# SCH_Flight-Computer-V2_2024-07-15.net
KiCad netlist of a schematic drawn in EasyEDA
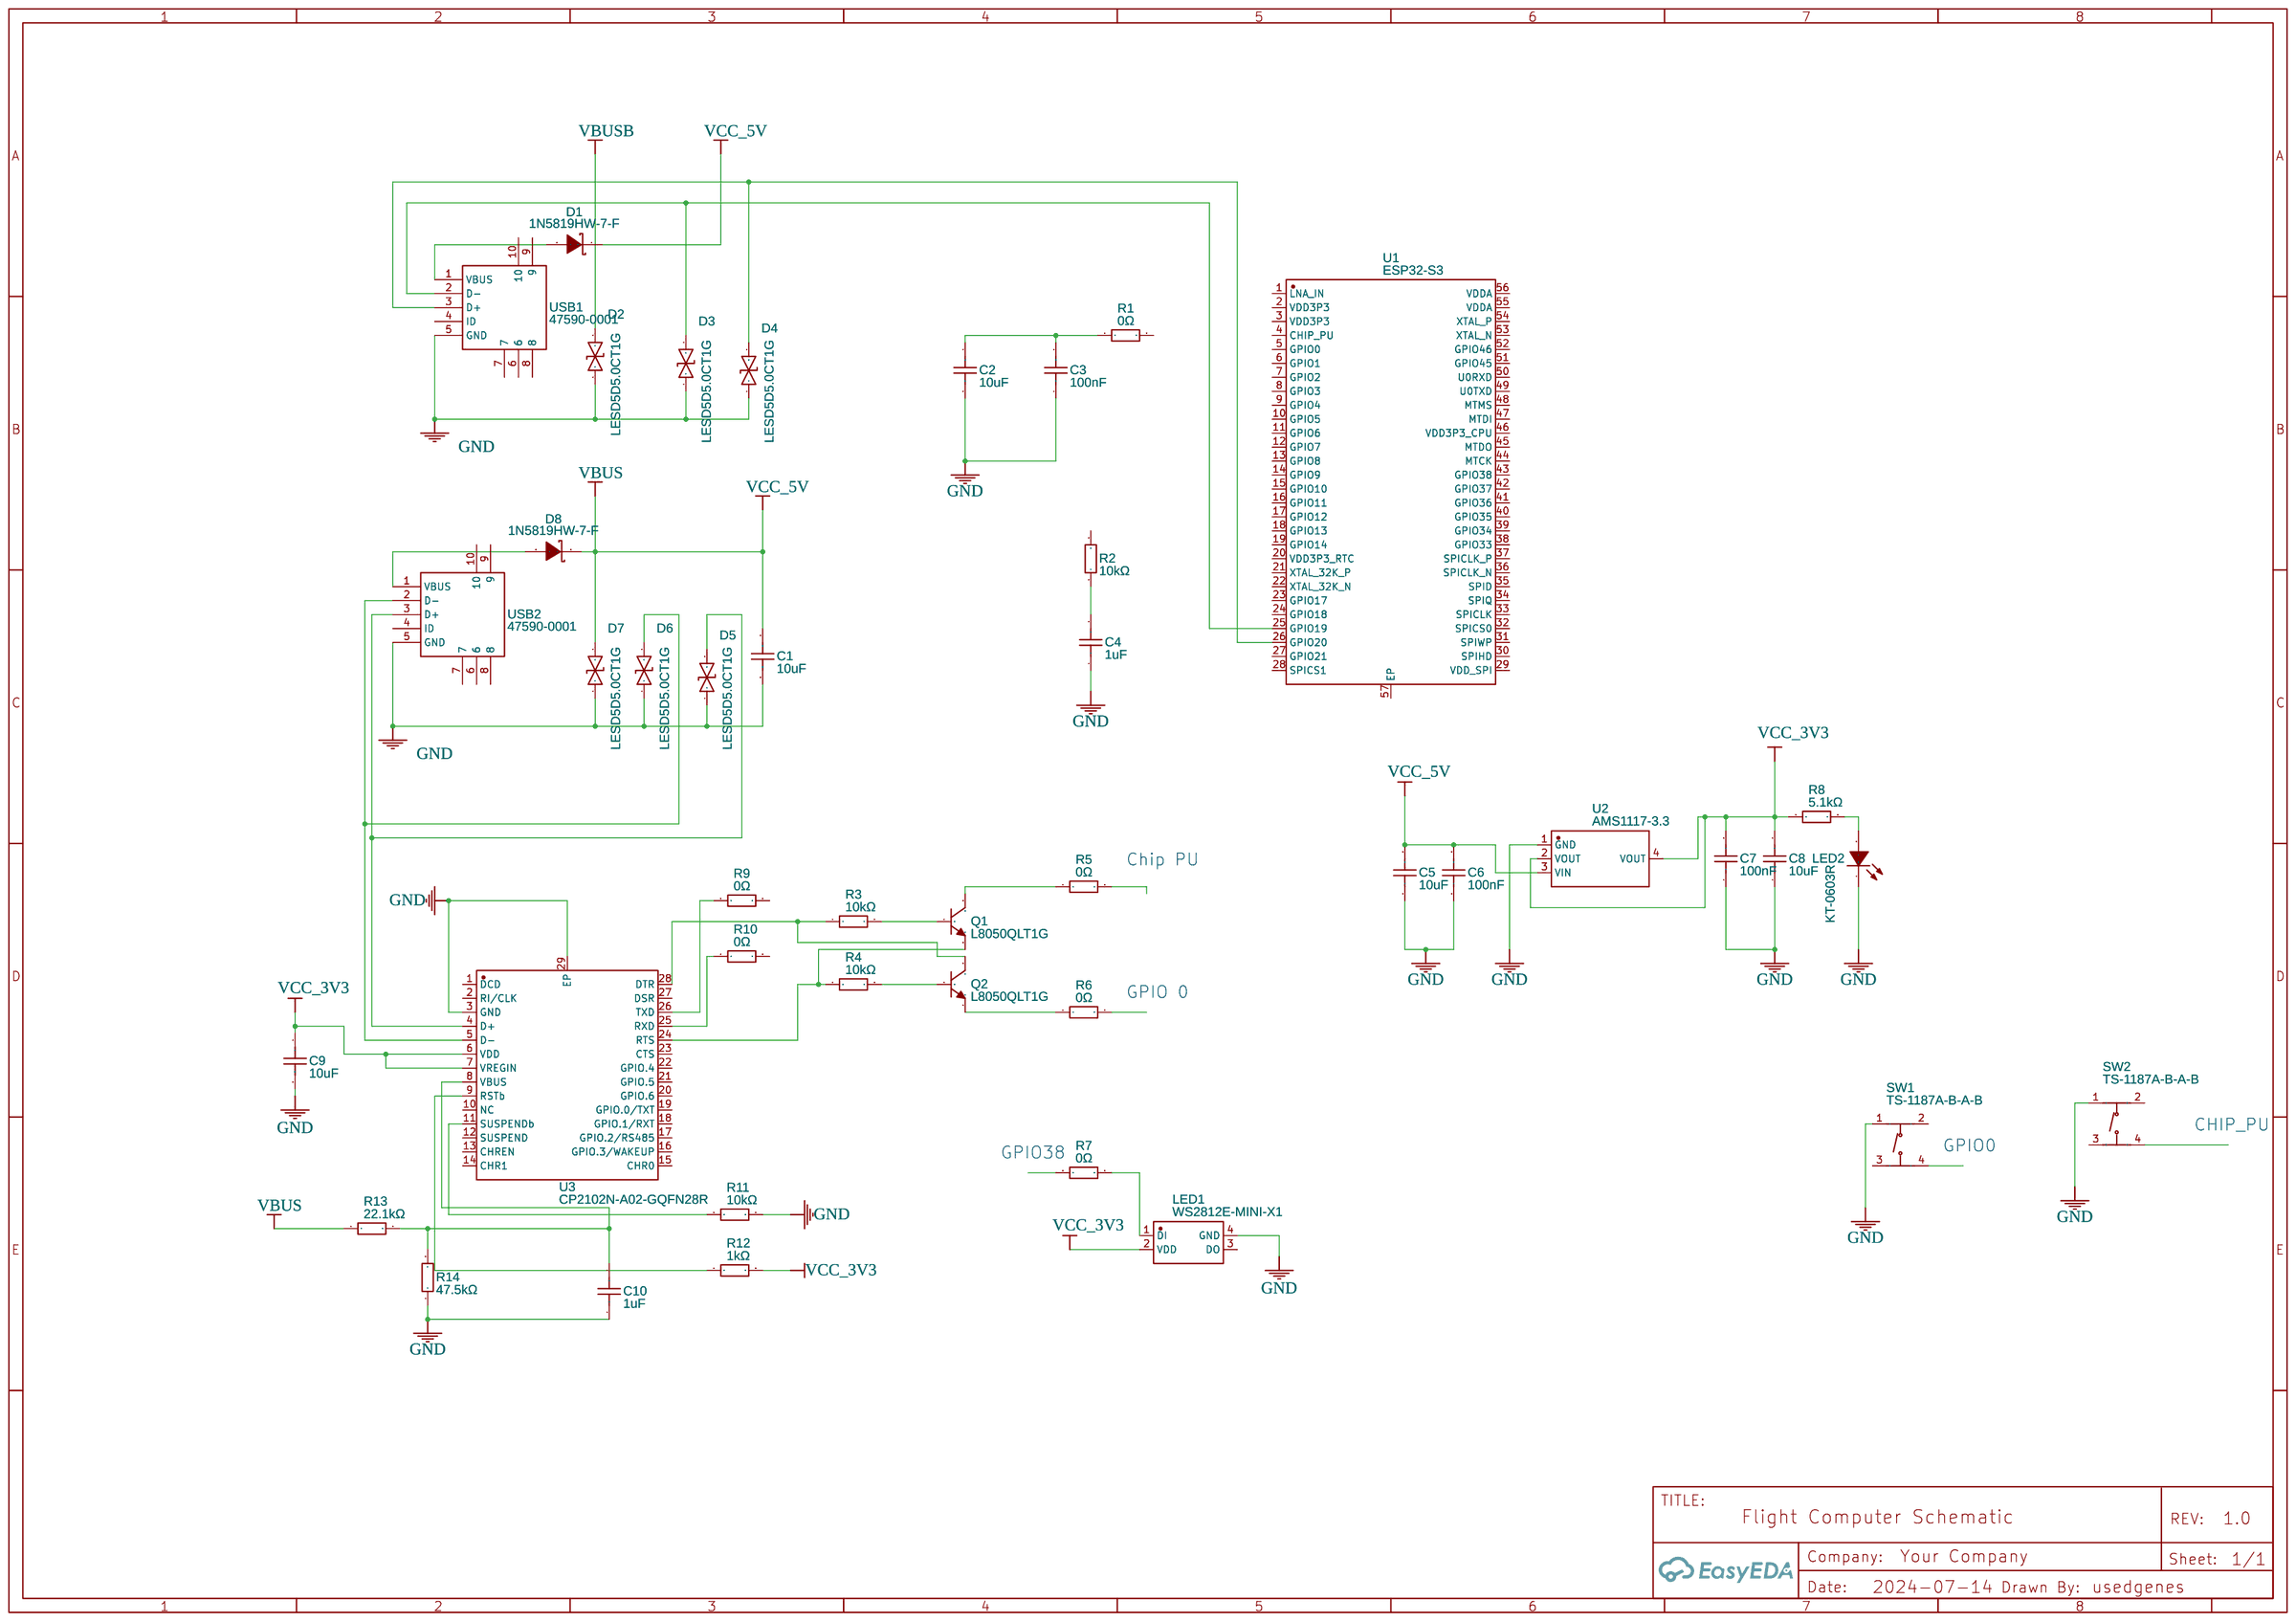
[diagram p0: schematic sheet]

(export (version "E")
  (design (tool "Eeschema 10.0.6"))
  (components
    (comp (ref "C1")
      (value "10uF")
      (fields
        (field (name "Manufacturer Part") "CL10A106KP8NNNC")
        (field (name "Manufacturer") "SAMSUNG(三星)")
      )
      (libsource (lib "") (part "CL10A106KP8NNNC"))
    )
    (comp (ref "C2")
      (value "10uF")
      (fields
        (field (name "Manufacturer Part") "CL10A106KP8NNNC")
        (field (name "Manufacturer") "SAMSUNG(三星)")
      )
      (libsource (lib "") (part "CL10A106KP8NNNC"))
    )
    (comp (ref "C3")
      (value "100nF")
      (fields
        (field (name "Manufacturer Part") "CC0603KRX7R9BB104")
        (field (name "Manufacturer") "YAGEO(国巨)")
      )
      (libsource (lib "") (part "CC0603KRX7R9BB104"))
    )
    (comp (ref "C4")
      (value "1uF")
      (fields
        (field (name "Manufacturer Part") "CL10A105KB8NNNC")
        (field (name "Manufacturer") "SAMSUNG(三星)")
      )
      (libsource (lib "") (part "CL10A105KB8NNNC"))
    )
    (comp (ref "C5")
      (value "10uF")
      (fields
        (field (name "Manufacturer Part") "CL10A106KP8NNNC")
        (field (name "Manufacturer") "SAMSUNG(三星)")
      )
      (libsource (lib "") (part "CL10A106KP8NNNC_1"))
    )
    (comp (ref "C6")
      (value "100nF")
      (fields
        (field (name "Manufacturer Part") "CC0603KRX7R9BB104")
        (field (name "Manufacturer") "YAGEO(国巨)")
      )
      (libsource (lib "") (part "CC0603KRX7R9BB104"))
    )
    (comp (ref "C7")
      (value "100nF")
      (fields
        (field (name "Manufacturer Part") "CC0603KRX7R9BB104")
        (field (name "Manufacturer") "YAGEO(国巨)")
      )
      (libsource (lib "") (part "CC0603KRX7R9BB104"))
    )
    (comp (ref "C8")
      (value "10uF")
      (fields
        (field (name "Manufacturer Part") "CL10A106KP8NNNC")
        (field (name "Manufacturer") "SAMSUNG(三星)")
      )
      (libsource (lib "") (part "CL10A106KP8NNNC_1"))
    )
    (comp (ref "C9")
      (value "10uF")
      (fields
        (field (name "Manufacturer Part") "CL10A106KP8NNNC")
        (field (name "Manufacturer") "SAMSUNG(三星)")
      )
      (libsource (lib "") (part "CL10A106KP8NNNC"))
    )
    (comp (ref "C10")
      (value "1uF")
      (fields
        (field (name "Manufacturer Part") "CL10A105KB8NNNC")
        (field (name "Manufacturer") "SAMSUNG(三星)")
      )
      (libsource (lib "") (part "CL10A105KB8NNNC"))
    )
    (comp (ref "D1")
      (value "1N5819HW-7-F")
      (fields (field (name "Manufacturer") "DIODES(美台)"))
      (libsource (lib "") (part "1N5819HW-7-F"))
    )
    (comp (ref "D2")
      (value "LESD5D5.0CT1G")
      (fields (field (name "Manufacturer") "LRC(乐山无线电)"))
      (libsource (lib "") (part "LESD5D5.0CT1G"))
    )
    (comp (ref "D3")
      (value "LESD5D5.0CT1G")
      (fields (field (name "Manufacturer") "LRC(乐山无线电)"))
      (libsource (lib "") (part "LESD5D5.0CT1G"))
    )
    (comp (ref "D4")
      (value "LESD5D5.0CT1G")
      (fields (field (name "Manufacturer") "LRC(乐山无线电)"))
      (libsource (lib "") (part "LESD5D5.0CT1G"))
    )
    (comp (ref "D5")
      (value "LESD5D5.0CT1G")
      (fields (field (name "Manufacturer") "LRC(乐山无线电)"))
      (libsource (lib "") (part "LESD5D5.0CT1G"))
    )
    (comp (ref "D6")
      (value "LESD5D5.0CT1G")
      (fields (field (name "Manufacturer") "LRC(乐山无线电)"))
      (libsource (lib "") (part "LESD5D5.0CT1G"))
    )
    (comp (ref "D7")
      (value "LESD5D5.0CT1G")
      (fields (field (name "Manufacturer") "LRC(乐山无线电)"))
      (libsource (lib "") (part "LESD5D5.0CT1G"))
    )
    (comp (ref "D8")
      (value "1N5819HW-7-F")
      (fields (field (name "Manufacturer") "DIODES(美台)"))
      (libsource (lib "") (part "1N5819HW-7-F"))
    )
    (comp (ref "LED1")
      (value "WS2812E-MINI-X1")
      (fields (field (name "Manufacturer") "worldsemi"))
      (libsource (lib "") (part "WS2812E-MINI-X1"))
    )
    (comp (ref "LED2")
      (value "KT-0603R")
      (fields (field (name "Manufacturer") "KENTO"))
      (libsource (lib "") (part "KT-0603R"))
    )
    (comp (ref "Q1")
      (value "L8050QLT1G")
      (fields (field (name "Manufacturer") "LRC(乐山无线电)"))
      (libsource (lib "") (part "L8050QLT1G"))
    )
    (comp (ref "Q2")
      (value "L8050QLT1G")
      (fields (field (name "Manufacturer") "LRC(乐山无线电)"))
      (libsource (lib "") (part "L8050QLT1G"))
    )
    (comp (ref "R1")
      (value "0Ω")
      (fields
        (field (name "Manufacturer Part") "0402WGF0000TCE")
        (field (name "Manufacturer") "UNI-ROYAL(厚声)")
      )
      (libsource (lib "") (part "0402WGF0000TCE"))
    )
    (comp (ref "R2")
      (value "10kΩ")
      (fields
        (field (name "Manufacturer Part") "0603WAF1002T5E")
        (field (name "Manufacturer") "UNI-ROYAL(厚声)")
      )
      (libsource (lib "") (part "0603WAF1002T5E_1"))
    )
    (comp (ref "R3")
      (value "10kΩ")
      (fields
        (field (name "Manufacturer Part") "0603WAF1002T5E")
        (field (name "Manufacturer") "UNI-ROYAL(厚声)")
      )
      (libsource (lib "") (part "0603WAF1002T5E"))
    )
    (comp (ref "R4")
      (value "10kΩ")
      (fields
        (field (name "Manufacturer Part") "0603WAF1002T5E")
        (field (name "Manufacturer") "UNI-ROYAL(厚声)")
      )
      (libsource (lib "") (part "0603WAF1002T5E"))
    )
    (comp (ref "R5")
      (value "0Ω")
      (fields
        (field (name "Manufacturer Part") "0402WGF0000TCE")
        (field (name "Manufacturer") "UNI-ROYAL(厚声)")
      )
      (libsource (lib "") (part "0402WGF0000TCE"))
    )
    (comp (ref "R6")
      (value "0Ω")
      (fields
        (field (name "Manufacturer Part") "0402WGF0000TCE")
        (field (name "Manufacturer") "UNI-ROYAL(厚声)")
      )
      (libsource (lib "") (part "0402WGF0000TCE"))
    )
    (comp (ref "R7")
      (value "0Ω")
      (fields
        (field (name "Manufacturer Part") "0402WGF0000TCE")
        (field (name "Manufacturer") "UNI-ROYAL(厚声)")
      )
      (libsource (lib "") (part "0402WGF0000TCE"))
    )
    (comp (ref "R8")
      (value "5.1kΩ")
      (fields
        (field (name "Manufacturer Part") "0603WAF5101T5E")
        (field (name "Manufacturer") "UNI-ROYAL(厚声)")
      )
      (libsource (lib "") (part "0603WAF5101T5E"))
    )
    (comp (ref "R9")
      (value "0Ω")
      (fields
        (field (name "Manufacturer Part") "0402WGF0000TCE")
        (field (name "Manufacturer") "UNI-ROYAL(厚声)")
      )
      (libsource (lib "") (part "0402WGF0000TCE"))
    )
    (comp (ref "R10")
      (value "0Ω")
      (fields
        (field (name "Manufacturer Part") "0402WGF0000TCE")
        (field (name "Manufacturer") "UNI-ROYAL(厚声)")
      )
      (libsource (lib "") (part "0402WGF0000TCE"))
    )
    (comp (ref "R11")
      (value "10kΩ")
      (fields
        (field (name "Manufacturer Part") "0603WAF1002T5E")
        (field (name "Manufacturer") "UNI-ROYAL(厚声)")
      )
      (libsource (lib "") (part "0603WAF1002T5E"))
    )
    (comp (ref "R12")
      (value "1kΩ")
      (fields
        (field (name "Manufacturer Part") "0603WAF1001T5E")
        (field (name "Manufacturer") "UNI-ROYAL(厚声)")
      )
      (libsource (lib "") (part "0603WAF1001T5E"))
    )
    (comp (ref "R13")
      (value "22.1kΩ")
      (fields
        (field (name "Manufacturer Part") "0402WGF2212TCE")
        (field (name "Manufacturer") "UNI-ROYAL(厚声)")
      )
      (libsource (lib "") (part "0402WGF2212TCE"))
    )
    (comp (ref "R14")
      (value "47.5kΩ")
      (fields
        (field (name "Manufacturer Part") "0603WAF4752T5E")
        (field (name "Manufacturer") "UNI-ROYAL(厚声)")
      )
      (libsource (lib "") (part "0603WAF4752T5E"))
    )
    (comp (ref "SW1")
      (value "TS-1187A-B-A-B")
      (fields (field (name "Manufacturer") "XKB Connectivity(中国星坤)"))
      (libsource (lib "") (part "TS-1187A-B-A-B"))
    )
    (comp (ref "SW2")
      (value "TS-1187A-B-A-B")
      (fields (field (name "Manufacturer") "XKB Connectivity(中国星坤)"))
      (libsource (lib "") (part "TS-1187A-B-A-B"))
    )
    (comp (ref "U1")
      (value "ESP32-S3")
      (fields (field (name "Manufacturer") "ESPRESSIF(乐鑫)"))
      (libsource (lib "") (part "ESP32-S3"))
    )
    (comp (ref "U2")
      (value "AMS1117-3.3")
      (fields (field (name "Manufacturer") "AMS"))
      (libsource (lib "") (part "AMS1117-3.3"))
    )
    (comp (ref "U3")
      (value "CP2102N-A02-GQFN28R")
      (fields (field (name "Manufacturer") "SKYWORKS/SILICON LABS(芯科)"))
      (libsource (lib "") (part "CP2102N-A02-GQFN28R"))
    )
    (comp (ref "USB1")
      (value "47590-0001")
      (fields (field (name "Manufacturer Part") "475900001") (field (name "Manufacturer") "MOLEX"))
      (libsource (lib "") (part "47590-0001"))
    )
    (comp (ref "USB2")
      (value "47590-0001")
      (fields (field (name "Manufacturer Part") "475900001") (field (name "Manufacturer") "MOLEX"))
      (libsource (lib "") (part "47590-0001"))
    )
  )
  (nets
    (net (code "1") (name "GND") (class "Default")
      (node (ref "C1") (pin "2") (pinfunction "2_2") (pintype "unspecified"))
      (node (ref "C10") (pin "1") (pinfunction "1_1") (pintype "unspecified"))
      (node (ref "C2") (pin "2") (pinfunction "2_2") (pintype "unspecified"))
      (node (ref "C3") (pin "1") (pinfunction "1_1") (pintype "unspecified"))
      (node (ref "C4") (pin "1") (pinfunction "1_1") (pintype "unspecified"))
      (node (ref "C5") (pin "1") (pinfunction "1_1") (pintype "unspecified"))
      (node (ref "C6") (pin "1") (pinfunction "1_1") (pintype "unspecified"))
      (node (ref "C7") (pin "1") (pinfunction "1_1") (pintype "unspecified"))
      (node (ref "C8") (pin "1") (pinfunction "1_1") (pintype "unspecified"))
      (node (ref "C9") (pin "2") (pinfunction "2_2") (pintype "unspecified"))
      (node (ref "D2") (pin "1") (pinfunction "1_1") (pintype "unspecified"))
      (node (ref "D3") (pin "1") (pinfunction "1_1") (pintype "unspecified"))
      (node (ref "D4") (pin "1") (pinfunction "1_1") (pintype "unspecified"))
      (node (ref "D5") (pin "1") (pinfunction "1_1") (pintype "unspecified"))
      (node (ref "D6") (pin "1") (pinfunction "1_1") (pintype "unspecified"))
      (node (ref "D7") (pin "1") (pinfunction "1_1") (pintype "unspecified"))
      (node (ref "LED1") (pin "4") (pinfunction "GND_4") (pintype "unspecified"))
      (node (ref "LED2") (pin "1") (pinfunction "K_1") (pintype "unspecified"))
      (node (ref "R11") (pin "2") (pinfunction "2_2") (pintype "input"))
      (node (ref "R14") (pin "1") (pinfunction "1_1") (pintype "input"))
      (node (ref "SW1") (pin "1") (pinfunction "A_1") (pintype "unspecified"))
      (node (ref "SW2") (pin "1") (pinfunction "A_1") (pintype "unspecified"))
      (node (ref "U2") (pin "1") (pinfunction "GND_1") (pintype "unspecified"))
      (node (ref "U3") (pin "29") (pinfunction "EP_29") (pintype "unspecified"))
      (node (ref "U3") (pin "3") (pinfunction "GND_3") (pintype "unspecified"))
      (node (ref "USB1") (pin "5") (pinfunction "GND_5") (pintype "unspecified"))
      (node (ref "USB2") (pin "5") (pinfunction "GND_5") (pintype "unspecified"))
    )
    (net (code "2") (name "Net-(C2-Pad1)") (class "Default")
      (node (ref "C2") (pin "1") (pinfunction "1_1") (pintype "unspecified"))
      (node (ref "C3") (pin "2") (pinfunction "2_2") (pintype "unspecified"))
      (node (ref "R1") (pin "1") (pinfunction "1_1") (pintype "input"))
    )
    (net (code "3") (name "Net-(C4-Pad2)") (class "Default")
      (node (ref "C4") (pin "2") (pinfunction "2_2") (pintype "unspecified"))
      (node (ref "R2") (pin "1") (pinfunction "1_1") (pintype "input"))
    )
    (net (code "4") (name "Net-(D1-A)") (class "Default")
      (node (ref "D1") (pin "2") (pinfunction "A_2") (pintype "unspecified"))
      (node (ref "USB1") (pin "1") (pinfunction "VBUS_1") (pintype "unspecified"))
    )
    (net (code "5") (name "Net-(D8-A)") (class "Default")
      (node (ref "D8") (pin "2") (pinfunction "A_2") (pintype "unspecified"))
      (node (ref "USB2") (pin "1") (pinfunction "VBUS_1") (pintype "unspecified"))
    )
    (net (code "6") (name "Net-(LED1-DI)") (class "Default")
      (node (ref "LED1") (pin "1") (pinfunction "DI_1") (pintype "unspecified"))
      (node (ref "R7") (pin "2") (pinfunction "2_2") (pintype "input"))
    )
    (net (code "7") (name "Net-(LED2-A)") (class "Default")
      (node (ref "LED2") (pin "2") (pinfunction "A_2") (pintype "unspecified"))
      (node (ref "R8") (pin "2") (pinfunction "2_2") (pintype "input"))
    )
    (net (code "8") (name "Net-(Q1-B)") (class "Default")
      (node (ref "Q1") (pin "1") (pinfunction "B_1") (pintype "unspecified"))
      (node (ref "R3") (pin "2") (pinfunction "2_2") (pintype "input"))
    )
    (net (code "9") (name "Net-(Q1-C)") (class "Default")
      (node (ref "Q1") (pin "3") (pinfunction "C_3") (pintype "unspecified"))
      (node (ref "R5") (pin "1") (pinfunction "1_1") (pintype "input"))
    )
    (net (code "10") (name "Net-(Q1-E)") (class "Default")
      (node (ref "Q1") (pin "2") (pinfunction "E_2") (pintype "unspecified"))
      (node (ref "R4") (pin "1") (pinfunction "1_1") (pintype "input"))
      (node (ref "U3") (pin "24") (pinfunction "RTS_24") (pintype "unspecified"))
    )
    (net (code "11") (name "Net-(Q2-B)") (class "Default")
      (node (ref "Q2") (pin "1") (pinfunction "B_1") (pintype "unspecified"))
      (node (ref "R4") (pin "2") (pinfunction "2_2") (pintype "input"))
    )
    (net (code "12") (name "Net-(Q2-C)") (class "Default")
      (node (ref "Q2") (pin "3") (pinfunction "C_3") (pintype "unspecified"))
      (node (ref "R3") (pin "1") (pinfunction "1_1") (pintype "input"))
      (node (ref "U3") (pin "28") (pinfunction "DTR_28") (pintype "unspecified"))
    )
    (net (code "13") (name "Net-(Q2-E)") (class "Default")
      (node (ref "Q2") (pin "2") (pinfunction "E_2") (pintype "unspecified"))
      (node (ref "R6") (pin "1") (pinfunction "1_1") (pintype "input"))
    )
    (net (code "14") (name "Net-(U1-GPIO19)") (class "Default")
      (node (ref "D3") (pin "2") (pinfunction "2_2") (pintype "unspecified"))
      (node (ref "U1") (pin "25") (pinfunction "GPIO19_25") (pintype "unspecified"))
      (node (ref "USB1") (pin "2") (pinfunction "D-_2") (pintype "unspecified"))
    )
    (net (code "15") (name "Net-(U1-GPIO20)") (class "Default")
      (node (ref "D4") (pin "2") (pinfunction "2_2") (pintype "unspecified"))
      (node (ref "U1") (pin "26") (pinfunction "GPIO20_26") (pintype "unspecified"))
      (node (ref "USB1") (pin "3") (pinfunction "D+_3") (pintype "unspecified"))
    )
    (net (code "16") (name "Net-(U3-D+)") (class "Default")
      (node (ref "D5") (pin "2") (pinfunction "2_2") (pintype "unspecified"))
      (node (ref "U3") (pin "4") (pinfunction "D+_4") (pintype "unspecified"))
      (node (ref "USB2") (pin "3") (pinfunction "D+_3") (pintype "unspecified"))
    )
    (net (code "17") (name "Net-(U3-D-)") (class "Default")
      (node (ref "D6") (pin "2") (pinfunction "2_2") (pintype "unspecified"))
      (node (ref "U3") (pin "5") (pinfunction "D-_5") (pintype "unspecified"))
      (node (ref "USB2") (pin "2") (pinfunction "D-_2") (pintype "unspecified"))
    )
    (net (code "18") (name "Net-(U3-RSTb)") (class "Default")
      (node (ref "R12") (pin "1") (pinfunction "1_1") (pintype "input"))
      (node (ref "U3") (pin "9") (pinfunction "RSTb_9") (pintype "unspecified"))
    )
    (net (code "19") (name "Net-(U3-RXD)") (class "Default")
      (node (ref "R10") (pin "1") (pinfunction "1_1") (pintype "input"))
      (node (ref "U3") (pin "25") (pinfunction "RXD_25") (pintype "unspecified"))
    )
    (net (code "20") (name "Net-(U3-SUSPENDb)") (class "Default")
      (node (ref "R11") (pin "1") (pinfunction "1_1") (pintype "input"))
      (node (ref "U3") (pin "11") (pinfunction "SUSPENDb_11") (pintype "unspecified"))
    )
    (net (code "21") (name "Net-(U3-TXD)") (class "Default")
      (node (ref "R9") (pin "1") (pinfunction "1_1") (pintype "input"))
      (node (ref "U3") (pin "26") (pinfunction "TXD_26") (pintype "unspecified"))
    )
    (net (code "22") (name "Net-(U3-VBUS)") (class "Default")
      (node (ref "C10") (pin "2") (pinfunction "2_2") (pintype "unspecified"))
      (node (ref "R13") (pin "2") (pinfunction "2_2") (pintype "input"))
      (node (ref "R14") (pin "2") (pinfunction "2_2") (pintype "input"))
      (node (ref "U3") (pin "8") (pinfunction "VBUS_8") (pintype "unspecified"))
    )
    (net (code "23") (name "VBUS") (class "Default")
      (node (ref "C1") (pin "1") (pinfunction "1_1") (pintype "unspecified"))
      (node (ref "C5") (pin "2") (pinfunction "2_2") (pintype "unspecified"))
      (node (ref "C6") (pin "2") (pinfunction "2_2") (pintype "unspecified"))
      (node (ref "D1") (pin "1") (pinfunction "K_1") (pintype "unspecified"))
      (node (ref "D7") (pin "2") (pinfunction "2_2") (pintype "unspecified"))
      (node (ref "D8") (pin "1") (pinfunction "K_1") (pintype "unspecified"))
      (node (ref "R13") (pin "1") (pinfunction "1_1") (pintype "input"))
      (node (ref "U2") (pin "3") (pinfunction "VIN_3") (pintype "unspecified"))
    )
    (net (code "24") (name "VBUSB") (class "Default")
      (node (ref "D2") (pin "2") (pinfunction "2_2") (pintype "unspecified"))
    )
    (net (code "25") (name "VCC_3V3") (class "Default")
      (node (ref "C7") (pin "2") (pinfunction "2_2") (pintype "unspecified"))
      (node (ref "C8") (pin "2") (pinfunction "2_2") (pintype "unspecified"))
      (node (ref "C9") (pin "1") (pinfunction "1_1") (pintype "unspecified"))
      (node (ref "LED1") (pin "2") (pinfunction "VDD_2") (pintype "unspecified"))
      (node (ref "R12") (pin "2") (pinfunction "2_2") (pintype "input"))
      (node (ref "R8") (pin "1") (pinfunction "1_1") (pintype "input"))
      (node (ref "U2") (pin "2") (pinfunction "VOUT_2") (pintype "unspecified"))
      (node (ref "U2") (pin "4") (pinfunction "VOUT_4") (pintype "unspecified"))
      (node (ref "U3") (pin "6") (pinfunction "VDD_6") (pintype "unspecified"))
      (node (ref "U3") (pin "7") (pinfunction "VREGIN_7") (pintype "unspecified"))
    )
    (net (code "26") (name "unconnected-(LED1-DO-Pad3)") (class "Default")
      (node (ref "LED1") (pin "3") (pinfunction "DO_3") (pintype "unspecified"))
    )
    (net (code "27") (name "unconnected-(R1-Pad2)") (class "Default")
      (node (ref "R1") (pin "2") (pinfunction "2_2") (pintype "input"))
    )
    (net (code "28") (name "unconnected-(R2-Pad2)") (class "Default")
      (node (ref "R2") (pin "2") (pinfunction "2_2") (pintype "input"))
    )
    (net (code "29") (name "unconnected-(R5-Pad2)") (class "Default")
      (node (ref "R5") (pin "2") (pinfunction "2_2") (pintype "input"))
    )
    (net (code "30") (name "unconnected-(R6-Pad2)") (class "Default")
      (node (ref "R6") (pin "2") (pinfunction "2_2") (pintype "input"))
    )
    (net (code "31") (name "unconnected-(R7-Pad1)") (class "Default")
      (node (ref "R7") (pin "1") (pinfunction "1_1") (pintype "input"))
    )
    (net (code "32") (name "unconnected-(R9-Pad2)") (class "Default")
      (node (ref "R9") (pin "2") (pinfunction "2_2") (pintype "input"))
    )
    (net (code "33") (name "unconnected-(R10-Pad2)") (class "Default")
      (node (ref "R10") (pin "2") (pinfunction "2_2") (pintype "input"))
    )
    (net (code "34") (name "unconnected-(SW1-B-Pad2)") (class "Default")
      (node (ref "SW1") (pin "2") (pinfunction "B_2") (pintype "unspecified"))
    )
    (net (code "35") (name "unconnected-(SW1-C-Pad3)") (class "Default")
      (node (ref "SW1") (pin "3") (pinfunction "C_3") (pintype "unspecified"))
    )
    (net (code "36") (name "unconnected-(SW1-D-Pad4)") (class "Default")
      (node (ref "SW1") (pin "4") (pinfunction "D_4") (pintype "unspecified"))
    )
    (net (code "37") (name "unconnected-(SW2-B-Pad2)") (class "Default")
      (node (ref "SW2") (pin "2") (pinfunction "B_2") (pintype "unspecified"))
    )
    (net (code "38") (name "unconnected-(SW2-C-Pad3)") (class "Default")
      (node (ref "SW2") (pin "3") (pinfunction "C_3") (pintype "unspecified"))
    )
    (net (code "39") (name "unconnected-(SW2-D-Pad4)") (class "Default")
      (node (ref "SW2") (pin "4") (pinfunction "D_4") (pintype "unspecified"))
    )
    (net (code "40") (name "unconnected-(U1-CHIP_PU-Pad4)") (class "Default")
      (node (ref "U1") (pin "4") (pinfunction "CHIP_PU_4") (pintype "unspecified"))
    )
    (net (code "41") (name "unconnected-(U1-EP-Pad57)") (class "Default")
      (node (ref "U1") (pin "57") (pinfunction "EP_57") (pintype "unspecified"))
    )
    (net (code "42") (name "unconnected-(U1-GPIO0-Pad5)") (class "Default")
      (node (ref "U1") (pin "5") (pinfunction "GPIO0_5") (pintype "unspecified"))
    )
    (net (code "43") (name "unconnected-(U1-GPIO1-Pad6)") (class "Default")
      (node (ref "U1") (pin "6") (pinfunction "GPIO1_6") (pintype "unspecified"))
    )
    (net (code "44") (name "unconnected-(U1-GPIO2-Pad7)") (class "Default")
      (node (ref "U1") (pin "7") (pinfunction "GPIO2_7") (pintype "unspecified"))
    )
    (net (code "45") (name "unconnected-(U1-GPIO3-Pad8)") (class "Default")
      (node (ref "U1") (pin "8") (pinfunction "GPIO3_8") (pintype "unspecified"))
    )
    (net (code "46") (name "unconnected-(U1-GPIO4-Pad9)") (class "Default")
      (node (ref "U1") (pin "9") (pinfunction "GPIO4_9") (pintype "unspecified"))
    )
    (net (code "47") (name "unconnected-(U1-GPIO5-Pad10)") (class "Default")
      (node (ref "U1") (pin "10") (pinfunction "GPIO5_10") (pintype "unspecified"))
    )
    (net (code "48") (name "unconnected-(U1-GPIO6-Pad11)") (class "Default")
      (node (ref "U1") (pin "11") (pinfunction "GPIO6_11") (pintype "unspecified"))
    )
    (net (code "49") (name "unconnected-(U1-GPIO7-Pad12)") (class "Default")
      (node (ref "U1") (pin "12") (pinfunction "GPIO7_12") (pintype "unspecified"))
    )
    (net (code "50") (name "unconnected-(U1-GPIO8-Pad13)") (class "Default")
      (node (ref "U1") (pin "13") (pinfunction "GPIO8_13") (pintype "unspecified"))
    )
    (net (code "51") (name "unconnected-(U1-GPIO9-Pad14)") (class "Default")
      (node (ref "U1") (pin "14") (pinfunction "GPIO9_14") (pintype "unspecified"))
    )
    (net (code "52") (name "unconnected-(U1-GPIO10-Pad15)") (class "Default")
      (node (ref "U1") (pin "15") (pinfunction "GPIO10_15") (pintype "unspecified"))
    )
    (net (code "53") (name "unconnected-(U1-GPIO11-Pad16)") (class "Default")
      (node (ref "U1") (pin "16") (pinfunction "GPIO11_16") (pintype "unspecified"))
    )
    (net (code "54") (name "unconnected-(U1-GPIO12-Pad17)") (class "Default")
      (node (ref "U1") (pin "17") (pinfunction "GPIO12_17") (pintype "unspecified"))
    )
    (net (code "55") (name "unconnected-(U1-GPIO13-Pad18)") (class "Default")
      (node (ref "U1") (pin "18") (pinfunction "GPIO13_18") (pintype "unspecified"))
    )
    (net (code "56") (name "unconnected-(U1-GPIO14-Pad19)") (class "Default")
      (node (ref "U1") (pin "19") (pinfunction "GPIO14_19") (pintype "unspecified"))
    )
    (net (code "57") (name "unconnected-(U1-GPIO17-Pad23)") (class "Default")
      (node (ref "U1") (pin "23") (pinfunction "GPIO17_23") (pintype "unspecified"))
    )
    (net (code "58") (name "unconnected-(U1-GPIO18-Pad24)") (class "Default")
      (node (ref "U1") (pin "24") (pinfunction "GPIO18_24") (pintype "unspecified"))
    )
    (net (code "59") (name "unconnected-(U1-GPIO21-Pad27)") (class "Default")
      (node (ref "U1") (pin "27") (pinfunction "GPIO21_27") (pintype "unspecified"))
    )
    (net (code "60") (name "unconnected-(U1-GPIO33-Pad38)") (class "Default")
      (node (ref "U1") (pin "38") (pinfunction "GPIO33_38") (pintype "unspecified"))
    )
    (net (code "61") (name "unconnected-(U1-GPIO34-Pad39)") (class "Default")
      (node (ref "U1") (pin "39") (pinfunction "GPIO34_39") (pintype "unspecified"))
    )
    (net (code "62") (name "unconnected-(U1-GPIO35-Pad40)") (class "Default")
      (node (ref "U1") (pin "40") (pinfunction "GPIO35_40") (pintype "unspecified"))
    )
    (net (code "63") (name "unconnected-(U1-GPIO36-Pad41)") (class "Default")
      (node (ref "U1") (pin "41") (pinfunction "GPIO36_41") (pintype "unspecified"))
    )
    (net (code "64") (name "unconnected-(U1-GPIO37-Pad42)") (class "Default")
      (node (ref "U1") (pin "42") (pinfunction "GPIO37_42") (pintype "unspecified"))
    )
    (net (code "65") (name "unconnected-(U1-GPIO38-Pad43)") (class "Default")
      (node (ref "U1") (pin "43") (pinfunction "GPIO38_43") (pintype "unspecified"))
    )
    (net (code "66") (name "unconnected-(U1-GPIO45-Pad51)") (class "Default")
      (node (ref "U1") (pin "51") (pinfunction "GPIO45_51") (pintype "unspecified"))
    )
    (net (code "67") (name "unconnected-(U1-GPIO46-Pad52)") (class "Default")
      (node (ref "U1") (pin "52") (pinfunction "GPIO46_52") (pintype "unspecified"))
    )
    (net (code "68") (name "unconnected-(U1-LNA_IN-Pad1)") (class "Default")
      (node (ref "U1") (pin "1") (pinfunction "LNA_IN_1") (pintype "unspecified"))
    )
    (net (code "69") (name "unconnected-(U1-MTCK-Pad44)") (class "Default")
      (node (ref "U1") (pin "44") (pinfunction "MTCK_44") (pintype "unspecified"))
    )
    (net (code "70") (name "unconnected-(U1-MTDI-Pad47)") (class "Default")
      (node (ref "U1") (pin "47") (pinfunction "MTDI_47") (pintype "unspecified"))
    )
    (net (code "71") (name "unconnected-(U1-MTDO-Pad45)") (class "Default")
      (node (ref "U1") (pin "45") (pinfunction "MTDO_45") (pintype "unspecified"))
    )
    (net (code "72") (name "unconnected-(U1-MTMS-Pad48)") (class "Default")
      (node (ref "U1") (pin "48") (pinfunction "MTMS_48") (pintype "unspecified"))
    )
    (net (code "73") (name "unconnected-(U1-SPICLK-Pad33)") (class "Default")
      (node (ref "U1") (pin "33") (pinfunction "SPICLK_33") (pintype "unspecified"))
    )
    (net (code "74") (name "unconnected-(U1-SPICLK_N-Pad36)") (class "Default")
      (node (ref "U1") (pin "36") (pinfunction "SPICLK_N_36") (pintype "unspecified"))
    )
    (net (code "75") (name "unconnected-(U1-SPICLK_P-Pad37)") (class "Default")
      (node (ref "U1") (pin "37") (pinfunction "SPICLK_P_37") (pintype "unspecified"))
    )
    (net (code "76") (name "unconnected-(U1-SPICS0-Pad32)") (class "Default")
      (node (ref "U1") (pin "32") (pinfunction "SPICS0_32") (pintype "unspecified"))
    )
    (net (code "77") (name "unconnected-(U1-SPICS1-Pad28)") (class "Default")
      (node (ref "U1") (pin "28") (pinfunction "SPICS1_28") (pintype "unspecified"))
    )
    (net (code "78") (name "unconnected-(U1-SPID-Pad35)") (class "Default")
      (node (ref "U1") (pin "35") (pinfunction "SPID_35") (pintype "unspecified"))
    )
    (net (code "79") (name "unconnected-(U1-SPIHD-Pad30)") (class "Default")
      (node (ref "U1") (pin "30") (pinfunction "SPIHD_30") (pintype "unspecified"))
    )
    (net (code "80") (name "unconnected-(U1-SPIQ-Pad34)") (class "Default")
      (node (ref "U1") (pin "34") (pinfunction "SPIQ_34") (pintype "unspecified"))
    )
    (net (code "81") (name "unconnected-(U1-SPIWP-Pad31)") (class "Default")
      (node (ref "U1") (pin "31") (pinfunction "SPIWP_31") (pintype "unspecified"))
    )
    (net (code "82") (name "unconnected-(U1-U0RXD-Pad50)") (class "Default")
      (node (ref "U1") (pin "50") (pinfunction "U0RXD_50") (pintype "unspecified"))
    )
    (net (code "83") (name "unconnected-(U1-U0TXD-Pad49)") (class "Default")
      (node (ref "U1") (pin "49") (pinfunction "U0TXD_49") (pintype "unspecified"))
    )
    (net (code "84") (name "unconnected-(U1-VDD3P3-Pad2)") (class "Default")
      (node (ref "U1") (pin "2") (pinfunction "VDD3P3_2") (pintype "unspecified"))
    )
    (net (code "85") (name "unconnected-(U1-VDD3P3-Pad3)") (class "Default")
      (node (ref "U1") (pin "3") (pinfunction "VDD3P3_3") (pintype "unspecified"))
    )
    (net (code "86") (name "unconnected-(U1-VDD3P3_CPU-Pad46)") (class "Default")
      (node (ref "U1") (pin "46") (pinfunction "VDD3P3_CPU_46") (pintype "unspecified"))
    )
    (net (code "87") (name "unconnected-(U1-VDD3P3_RTC-Pad20)") (class "Default")
      (node (ref "U1") (pin "20") (pinfunction "VDD3P3_RTC_20") (pintype "unspecified"))
    )
    (net (code "88") (name "unconnected-(U1-VDDA-Pad55)") (class "Default")
      (node (ref "U1") (pin "55") (pinfunction "VDDA_55") (pintype "unspecified"))
    )
    (net (code "89") (name "unconnected-(U1-VDDA-Pad56)") (class "Default")
      (node (ref "U1") (pin "56") (pinfunction "VDDA_56") (pintype "unspecified"))
    )
    (net (code "90") (name "unconnected-(U1-VDD_SPI-Pad29)") (class "Default")
      (node (ref "U1") (pin "29") (pinfunction "VDD_SPI_29") (pintype "unspecified"))
    )
    (net (code "91") (name "unconnected-(U1-XTAL_32K_N-Pad22)") (class "Default")
      (node (ref "U1") (pin "22") (pinfunction "XTAL_32K_N_22") (pintype "unspecified"))
    )
    (net (code "92") (name "unconnected-(U1-XTAL_32K_P-Pad21)") (class "Default")
      (node (ref "U1") (pin "21") (pinfunction "XTAL_32K_P_21") (pintype "unspecified"))
    )
    (net (code "93") (name "unconnected-(U1-XTAL_N-Pad53)") (class "Default")
      (node (ref "U1") (pin "53") (pinfunction "XTAL_N_53") (pintype "unspecified"))
    )
    (net (code "94") (name "unconnected-(U1-XTAL_P-Pad54)") (class "Default")
      (node (ref "U1") (pin "54") (pinfunction "XTAL_P_54") (pintype "unspecified"))
    )
    (net (code "95") (name "unconnected-(U3-CHR0-Pad15)") (class "Default")
      (node (ref "U3") (pin "15") (pinfunction "CHR0_15") (pintype "unspecified"))
    )
    (net (code "96") (name "unconnected-(U3-CHR1-Pad14)") (class "Default")
      (node (ref "U3") (pin "14") (pinfunction "CHR1_14") (pintype "unspecified"))
    )
    (net (code "97") (name "unconnected-(U3-CHREN-Pad13)") (class "Default")
      (node (ref "U3") (pin "13") (pinfunction "CHREN_13") (pintype "unspecified"))
    )
    (net (code "98") (name "unconnected-(U3-CTS-Pad23)") (class "Default")
      (node (ref "U3") (pin "23") (pinfunction "CTS_23") (pintype "unspecified"))
    )
    (net (code "99") (name "unconnected-(U3-DCD-Pad1)") (class "Default")
      (node (ref "U3") (pin "1") (pinfunction "DCD_1") (pintype "unspecified"))
    )
    (net (code "100") (name "unconnected-(U3-DSR-Pad27)") (class "Default")
      (node (ref "U3") (pin "27") (pinfunction "DSR_27") (pintype "unspecified"))
    )
    (net (code "101") (name "unconnected-(U3-GPIO.0{slash}TXT-Pad19)") (class "Default")
      (node (ref "U3") (pin "19") (pinfunction "GPIO.0/TXT_19") (pintype "unspecified"))
    )
    (net (code "102") (name "unconnected-(U3-GPIO.1{slash}RXT-Pad18)") (class "Default")
      (node (ref "U3") (pin "18") (pinfunction "GPIO.1/RXT_18") (pintype "unspecified"))
    )
    (net (code "103") (name "unconnected-(U3-GPIO.2{slash}RS485-Pad17)") (class "Default")
      (node (ref "U3") (pin "17") (pinfunction "GPIO.2/RS485_17") (pintype "unspecified"))
    )
    (net (code "104") (name "unconnected-(U3-GPIO.3{slash}WAKEUP-Pad16)") (class "Default")
      (node (ref "U3") (pin "16") (pinfunction "GPIO.3/WAKEUP_16") (pintype "unspecified"))
    )
    (net (code "105") (name "unconnected-(U3-GPIO.4-Pad22)") (class "Default")
      (node (ref "U3") (pin "22") (pinfunction "GPIO.4_22") (pintype "unspecified"))
    )
    (net (code "106") (name "unconnected-(U3-GPIO.5-Pad21)") (class "Default")
      (node (ref "U3") (pin "21") (pinfunction "GPIO.5_21") (pintype "unspecified"))
    )
    (net (code "107") (name "unconnected-(U3-GPIO.6-Pad20)") (class "Default")
      (node (ref "U3") (pin "20") (pinfunction "GPIO.6_20") (pintype "unspecified"))
    )
    (net (code "108") (name "unconnected-(U3-NC-Pad10)") (class "Default")
      (node (ref "U3") (pin "10") (pinfunction "NC_10") (pintype "unspecified"))
    )
    (net (code "109") (name "unconnected-(U3-RI{slash}CLK-Pad2)") (class "Default")
      (node (ref "U3") (pin "2") (pinfunction "RI/CLK_2") (pintype "unspecified"))
    )
    (net (code "110") (name "unconnected-(U3-SUSPEND-Pad12)") (class "Default")
      (node (ref "U3") (pin "12") (pinfunction "SUSPEND_12") (pintype "unspecified"))
    )
    (net (code "111") (name "unconnected-(USB1-ID-Pad4)") (class "Default")
      (node (ref "USB1") (pin "4") (pinfunction "ID_4") (pintype "unspecified"))
    )
    (net (code "112") (name "unconnected-(USB1-Pad6)") (class "Default")
      (node (ref "USB1") (pin "6") (pinfunction "6_6") (pintype "unspecified"))
    )
    (net (code "113") (name "unconnected-(USB1-Pad7)") (class "Default")
      (node (ref "USB1") (pin "7") (pinfunction "7_7") (pintype "unspecified"))
    )
    (net (code "114") (name "unconnected-(USB1-Pad8)") (class "Default")
      (node (ref "USB1") (pin "8") (pinfunction "8_8") (pintype "unspecified"))
    )
    (net (code "115") (name "unconnected-(USB1-Pad9)") (class "Default")
      (node (ref "USB1") (pin "9") (pinfunction "9_9") (pintype "unspecified"))
    )
    (net (code "116") (name "unconnected-(USB1-Pad10)") (class "Default")
      (node (ref "USB1") (pin "10") (pinfunction "10_10") (pintype "unspecified"))
    )
    (net (code "117") (name "unconnected-(USB2-ID-Pad4)") (class "Default")
      (node (ref "USB2") (pin "4") (pinfunction "ID_4") (pintype "unspecified"))
    )
    (net (code "118") (name "unconnected-(USB2-Pad6)") (class "Default")
      (node (ref "USB2") (pin "6") (pinfunction "6_6") (pintype "unspecified"))
    )
    (net (code "119") (name "unconnected-(USB2-Pad7)") (class "Default")
      (node (ref "USB2") (pin "7") (pinfunction "7_7") (pintype "unspecified"))
    )
    (net (code "120") (name "unconnected-(USB2-Pad8)") (class "Default")
      (node (ref "USB2") (pin "8") (pinfunction "8_8") (pintype "unspecified"))
    )
    (net (code "121") (name "unconnected-(USB2-Pad9)") (class "Default")
      (node (ref "USB2") (pin "9") (pinfunction "9_9") (pintype "unspecified"))
    )
    (net (code "122") (name "unconnected-(USB2-Pad10)") (class "Default")
      (node (ref "USB2") (pin "10") (pinfunction "10_10") (pintype "unspecified"))
    )
  )
)
